# connectors.net
KiCad netlist of a schematic drawn in Altium Designer
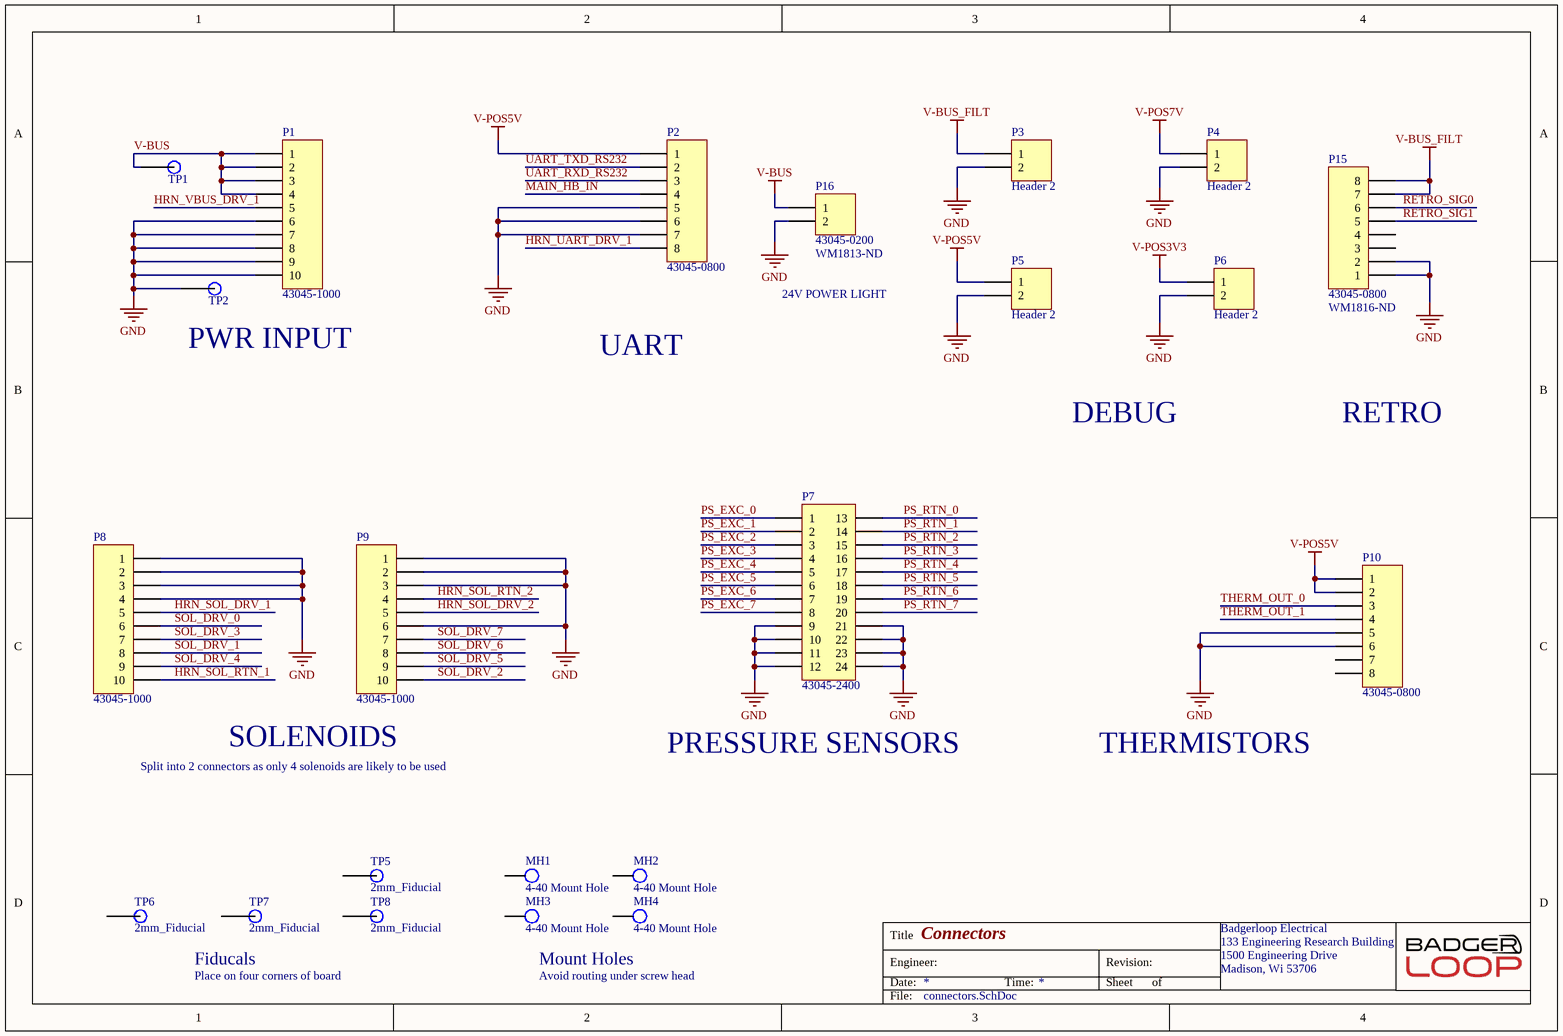
[diagram p0: connectors.SchDoc]

(export (version "E")
  (design (tool "Eeschema 10.0.6"))
  (components
    (comp (ref "MH1")
      (value "4-40 Mount Hole")
      (footprint "MH")
      (libsource (lib "misc") (part "4-40 Mount Hole"))
    )
    (comp (ref "MH2")
      (value "4-40 Mount Hole")
      (footprint "MH")
      (libsource (lib "misc") (part "4-40 Mount Hole"))
    )
    (comp (ref "MH3")
      (value "4-40 Mount Hole")
      (footprint "MH")
      (libsource (lib "misc") (part "4-40 Mount Hole"))
    )
    (comp (ref "MH4")
      (value "4-40 Mount Hole")
      (footprint "MH")
      (libsource (lib "misc") (part "4-40 Mount Hole"))
    )
    (comp (ref "P1")
      (value "43045-1000")
      (footprint "430451000")
      (description "GLOVE, POLYAMIDE, L/FREE, PU, SIZE 6 - More Details")
      (fields (field (name "MANUFACTURER") "Molex"))
      (libsource (lib "") (part "43045-1000_1"))
    )
    (comp (ref "P2")
      (value "43045-0800")
      (footprint "430450800")
      (description "CONN HEADER R/A 8POS 3MM")
      (fields (field (name "MANUFACTURER") "Molex"))
      (libsource (lib "connector") (part "43045-0800"))
    )
    (comp (ref "P3")
      (value "Header 2")
      (footprint "Pin Header 1x2 TH Pitch 2.54mm")
      (description "Header, 2-Pin")
      (fields (field (name "PUBLISHER") "Altium Limited"))
      (libsource (lib "connector") (part "Header 2"))
    )
    (comp (ref "P4")
      (value "Header 2")
      (footprint "Pin Header 1x2 TH Pitch 2.54mm")
      (description "Header, 2-Pin")
      (fields (field (name "PUBLISHER") "Altium Limited"))
      (libsource (lib "connector") (part "Header 2"))
    )
    (comp (ref "P5")
      (value "Header 2")
      (footprint "Pin Header 1x2 TH Pitch 2.54mm")
      (description "Header, 2-Pin")
      (fields (field (name "PUBLISHER") "Altium Limited"))
      (libsource (lib "connector") (part "Header 2"))
    )
    (comp (ref "P6")
      (value "Header 2")
      (footprint "Pin Header 1x2 TH Pitch 2.54mm")
      (description "Header, 2-Pin")
      (fields (field (name "PUBLISHER") "Altium Limited"))
      (libsource (lib "connector") (part "Header 2"))
    )
    (comp (ref "P7")
      (value "43045-2400")
      (footprint "430452400")
      (fields (field (name "MANUFACTURER") "Molex"))
      (libsource (lib "connector") (part "43045-2400"))
    )
    (comp (ref "P8")
      (value "43045-1000")
      (footprint "430451000")
      (description "GLOVE, POLYAMIDE, L/FREE, PU, SIZE 6 - More Details")
      (fields (field (name "MANUFACTURER") "Molex"))
      (libsource (lib "connector") (part "43045-1000"))
    )
    (comp (ref "P9")
      (value "43045-1000")
      (footprint "430451000")
      (description "GLOVE, POLYAMIDE, L/FREE, PU, SIZE 6 - More Details")
      (fields (field (name "MANUFACTURER") "Molex"))
      (libsource (lib "connector") (part "43045-1000"))
    )
    (comp (ref "P10")
      (value "43045-0800")
      (footprint "430450800")
      (description "CONN HEADER R/A 8POS 3MM")
      (fields (field (name "MANUFACTURER") "Molex"))
      (libsource (lib "connector") (part "43045-0800"))
    )
    (comp (ref "P15")
      (value "43045-0800")
      (footprint "430450800")
      (description "CONN HEADER R/A 8POS 3MM")
      (fields (field (name "MANUFACTURER") "Molex") (field (name "SUPPLIER PART NUMBER 1") "WM1816-ND"))
      (libsource (lib "") (part "43045-0800_1"))
    )
    (comp (ref "P16")
      (value "43045-0200")
      (footprint "430450200")
      (description "CONN HEADER R/A 2POS")
      (fields (field (name "MANUFACTURER") "Molex") (field (name "SUPPLIER PART NUMBER 1") "WM1813-ND"))
      (libsource (lib "connector") (part "43045-0200"))
    )
    (comp (ref "TP1")
      (value "TP")
      (footprint "Test Point")
      (description "SMD TEST POINT")
      (libsource (lib "misc") (part "TP"))
    )
    (comp (ref "TP2")
      (value "TP")
      (footprint "Test Point")
      (description "SMD TEST POINT")
      (libsource (lib "misc") (part "TP"))
    )
    (comp (ref "TP5")
      (value "2mm_Fiducial")
      (footprint "2mm_Fiducial")
      (libsource (lib "misc") (part "2mm_Fiducial"))
    )
    (comp (ref "TP6")
      (value "2mm_Fiducial")
      (footprint "2mm_Fiducial")
      (libsource (lib "misc") (part "2mm_Fiducial"))
    )
    (comp (ref "TP7")
      (value "2mm_Fiducial")
      (footprint "2mm_Fiducial")
      (libsource (lib "misc") (part "2mm_Fiducial"))
    )
    (comp (ref "TP8")
      (value "2mm_Fiducial")
      (footprint "2mm_Fiducial")
      (libsource (lib "misc") (part "2mm_Fiducial"))
    )
  )
  (nets
    (net (code "1") (name "/HRN_SOL_DRV_1") (class "Default")
      (node (ref "P8") (pin "5") (pinfunction "5_5") (pintype "passive"))
    )
    (net (code "2") (name "/HRN_SOL_DRV_2") (class "Default")
      (node (ref "P9") (pin "5") (pinfunction "5_5") (pintype "passive"))
    )
    (net (code "3") (name "/HRN_SOL_RTN_1") (class "Default")
      (node (ref "P8") (pin "10") (pinfunction "10_10") (pintype "passive"))
    )
    (net (code "4") (name "/HRN_SOL_RTN_2") (class "Default")
      (node (ref "P9") (pin "4") (pinfunction "4_4") (pintype "passive"))
    )
    (net (code "5") (name "/HRN_UART_DRV_1") (class "Default")
      (node (ref "P2") (pin "8") (pinfunction "8_8") (pintype "passive"))
    )
    (net (code "6") (name "/HRN_VBUS_DRV_1") (class "Default")
      (node (ref "P1") (pin "5") (pinfunction "5_5") (pintype "passive"))
    )
    (net (code "7") (name "/MAIN_HB_IN") (class "Default")
      (node (ref "P2") (pin "4") (pinfunction "4_4") (pintype "passive"))
    )
    (net (code "8") (name "/PS_EXC_0") (class "Default")
      (node (ref "P7") (pin "1") (pinfunction "1_1") (pintype "passive"))
    )
    (net (code "9") (name "/PS_EXC_1") (class "Default")
      (node (ref "P7") (pin "2") (pinfunction "2_2") (pintype "passive"))
    )
    (net (code "10") (name "/PS_EXC_2") (class "Default")
      (node (ref "P7") (pin "3") (pinfunction "3_3") (pintype "passive"))
    )
    (net (code "11") (name "/PS_EXC_3") (class "Default")
      (node (ref "P7") (pin "4") (pinfunction "4_4") (pintype "passive"))
    )
    (net (code "12") (name "/PS_EXC_4") (class "Default")
      (node (ref "P7") (pin "5") (pinfunction "5_5") (pintype "passive"))
    )
    (net (code "13") (name "/PS_EXC_5") (class "Default")
      (node (ref "P7") (pin "6") (pinfunction "6_6") (pintype "passive"))
    )
    (net (code "14") (name "/PS_EXC_6") (class "Default")
      (node (ref "P7") (pin "7") (pinfunction "7_7") (pintype "passive"))
    )
    (net (code "15") (name "/PS_EXC_7") (class "Default")
      (node (ref "P7") (pin "8") (pinfunction "8_8") (pintype "passive"))
    )
    (net (code "16") (name "/PS_RTN_0") (class "Default")
      (node (ref "P7") (pin "13") (pinfunction "13_13") (pintype "passive"))
    )
    (net (code "17") (name "/PS_RTN_1") (class "Default")
      (node (ref "P7") (pin "14") (pinfunction "14_14") (pintype "passive"))
    )
    (net (code "18") (name "/PS_RTN_2") (class "Default")
      (node (ref "P7") (pin "15") (pinfunction "15_15") (pintype "passive"))
    )
    (net (code "19") (name "/PS_RTN_3") (class "Default")
      (node (ref "P7") (pin "16") (pinfunction "16_16") (pintype "passive"))
    )
    (net (code "20") (name "/PS_RTN_4") (class "Default")
      (node (ref "P7") (pin "17") (pinfunction "17_17") (pintype "passive"))
    )
    (net (code "21") (name "/PS_RTN_5") (class "Default")
      (node (ref "P7") (pin "18") (pinfunction "18_18") (pintype "passive"))
    )
    (net (code "22") (name "/PS_RTN_6") (class "Default")
      (node (ref "P7") (pin "19") (pinfunction "19_19") (pintype "passive"))
    )
    (net (code "23") (name "/PS_RTN_7") (class "Default")
      (node (ref "P7") (pin "20") (pinfunction "20_20") (pintype "passive"))
    )
    (net (code "24") (name "/RETRO_SIG0") (class "Default")
      (node (ref "P15") (pin "6") (pinfunction "6_6") (pintype "passive"))
    )
    (net (code "25") (name "/RETRO_SIG1") (class "Default")
      (node (ref "P15") (pin "5") (pinfunction "5_5") (pintype "passive"))
    )
    (net (code "26") (name "/SOL_DRV_0") (class "Default")
      (node (ref "P8") (pin "6") (pinfunction "6_6") (pintype "passive"))
    )
    (net (code "27") (name "/SOL_DRV_1") (class "Default")
      (node (ref "P8") (pin "8") (pinfunction "8_8") (pintype "passive"))
    )
    (net (code "28") (name "/SOL_DRV_2") (class "Default")
      (node (ref "P9") (pin "10") (pinfunction "10_10") (pintype "passive"))
    )
    (net (code "29") (name "/SOL_DRV_3") (class "Default")
      (node (ref "P8") (pin "7") (pinfunction "7_7") (pintype "passive"))
    )
    (net (code "30") (name "/SOL_DRV_4") (class "Default")
      (node (ref "P8") (pin "9") (pinfunction "9_9") (pintype "passive"))
    )
    (net (code "31") (name "/SOL_DRV_5") (class "Default")
      (node (ref "P9") (pin "9") (pinfunction "9_9") (pintype "passive"))
    )
    (net (code "32") (name "/SOL_DRV_6") (class "Default")
      (node (ref "P9") (pin "8") (pinfunction "8_8") (pintype "passive"))
    )
    (net (code "33") (name "/SOL_DRV_7") (class "Default")
      (node (ref "P9") (pin "7") (pinfunction "7_7") (pintype "passive"))
    )
    (net (code "34") (name "/THERM_OUT_0") (class "Default")
      (node (ref "P10") (pin "3") (pinfunction "3_3") (pintype "passive"))
    )
    (net (code "35") (name "/THERM_OUT_1") (class "Default")
      (node (ref "P10") (pin "4") (pinfunction "4_4") (pintype "passive"))
    )
    (net (code "36") (name "/UART_RXD_RS232") (class "Default")
      (node (ref "P2") (pin "3") (pinfunction "3_3") (pintype "passive"))
    )
    (net (code "37") (name "/UART_TXD_RS232") (class "Default")
      (node (ref "P2") (pin "2") (pinfunction "2_2") (pintype "passive"))
    )
    (net (code "38") (name "GND") (class "Default")
      (node (ref "P1") (pin "10") (pinfunction "10_10") (pintype "passive"))
      (node (ref "P1") (pin "6") (pinfunction "6_6") (pintype "passive"))
      (node (ref "P1") (pin "7") (pinfunction "7_7") (pintype "passive"))
      (node (ref "P1") (pin "8") (pinfunction "8_8") (pintype "passive"))
      (node (ref "P1") (pin "9") (pinfunction "9_9") (pintype "passive"))
      (node (ref "P10") (pin "5") (pinfunction "5_5") (pintype "passive"))
      (node (ref "P10") (pin "6") (pinfunction "6_6") (pintype "passive"))
      (node (ref "P15") (pin "1") (pinfunction "1_1") (pintype "passive"))
      (node (ref "P15") (pin "2") (pinfunction "2_2") (pintype "passive"))
      (node (ref "P16") (pin "2") (pinfunction "2_2") (pintype "passive"))
      (node (ref "P2") (pin "5") (pinfunction "5_5") (pintype "passive"))
      (node (ref "P2") (pin "6") (pinfunction "6_6") (pintype "passive"))
      (node (ref "P2") (pin "7") (pinfunction "7_7") (pintype "passive"))
      (node (ref "P3") (pin "2") (pinfunction "2_2") (pintype "passive"))
      (node (ref "P4") (pin "2") (pinfunction "2_2") (pintype "passive"))
      (node (ref "P5") (pin "2") (pinfunction "2_2") (pintype "passive"))
      (node (ref "P6") (pin "2") (pinfunction "2_2") (pintype "passive"))
      (node (ref "P7") (pin "10") (pinfunction "10_10") (pintype "passive"))
      (node (ref "P7") (pin "11") (pinfunction "11_11") (pintype "passive"))
      (node (ref "P7") (pin "12") (pinfunction "12_12") (pintype "passive"))
      (node (ref "P7") (pin "21") (pinfunction "21_21") (pintype "passive"))
      (node (ref "P7") (pin "22") (pinfunction "22_22") (pintype "passive"))
      (node (ref "P7") (pin "23") (pinfunction "23_23") (pintype "passive"))
      (node (ref "P7") (pin "24") (pinfunction "24_24") (pintype "passive"))
      (node (ref "P7") (pin "9") (pinfunction "9_9") (pintype "passive"))
      (node (ref "P8") (pin "1") (pinfunction "1_1") (pintype "passive"))
      (node (ref "P8") (pin "2") (pinfunction "2_2") (pintype "passive"))
      (node (ref "P8") (pin "3") (pinfunction "3_3") (pintype "passive"))
      (node (ref "P8") (pin "4") (pinfunction "4_4") (pintype "passive"))
      (node (ref "P9") (pin "1") (pinfunction "1_1") (pintype "passive"))
      (node (ref "P9") (pin "2") (pinfunction "2_2") (pintype "passive"))
      (node (ref "P9") (pin "3") (pinfunction "3_3") (pintype "passive"))
      (node (ref "P9") (pin "6") (pinfunction "6_6") (pintype "passive"))
      (node (ref "TP2") (pin "1") (pinfunction "1_1") (pintype "passive"))
    )
    (net (code "39") (name "V-BUS") (class "Default")
      (node (ref "P1") (pin "1") (pinfunction "1_1") (pintype "passive"))
      (node (ref "P1") (pin "2") (pinfunction "2_2") (pintype "passive"))
      (node (ref "P1") (pin "3") (pinfunction "3_3") (pintype "passive"))
      (node (ref "P1") (pin "4") (pinfunction "4_4") (pintype "passive"))
      (node (ref "P16") (pin "1") (pinfunction "1_1") (pintype "passive"))
      (node (ref "TP1") (pin "1") (pinfunction "1_1") (pintype "passive"))
    )
    (net (code "40") (name "V-BUS_FILT") (class "Default")
      (node (ref "P15") (pin "7") (pinfunction "7_7") (pintype "passive"))
      (node (ref "P15") (pin "8") (pinfunction "8_8") (pintype "passive"))
      (node (ref "P3") (pin "1") (pinfunction "1_1") (pintype "passive"))
    )
    (net (code "41") (name "V-POS3V3") (class "Default")
      (node (ref "P6") (pin "1") (pinfunction "1_1") (pintype "passive"))
    )
    (net (code "42") (name "V-POS5V") (class "Default")
      (node (ref "P10") (pin "1") (pinfunction "1_1") (pintype "passive"))
      (node (ref "P10") (pin "2") (pinfunction "2_2") (pintype "passive"))
      (node (ref "P2") (pin "1") (pinfunction "1_1") (pintype "passive"))
      (node (ref "P5") (pin "1") (pinfunction "1_1") (pintype "passive"))
    )
    (net (code "43") (name "V-POS7V") (class "Default")
      (node (ref "P4") (pin "1") (pinfunction "1_1") (pintype "passive"))
    )
    (net (code "44") (name "unconnected-(MH1-Pad46)") (class "Default")
      (node (ref "MH1") (pin "46") (pinfunction "46_46") (pintype "passive"))
    )
    (net (code "45") (name "unconnected-(MH2-Pad46)") (class "Default")
      (node (ref "MH2") (pin "46") (pinfunction "46_46") (pintype "passive"))
    )
    (net (code "46") (name "unconnected-(MH3-Pad46)") (class "Default")
      (node (ref "MH3") (pin "46") (pinfunction "46_46") (pintype "passive"))
    )
    (net (code "47") (name "unconnected-(MH4-Pad46)") (class "Default")
      (node (ref "MH4") (pin "46") (pinfunction "46_46") (pintype "passive"))
    )
    (net (code "48") (name "unconnected-(P10-Pad7)") (class "Default")
      (node (ref "P10") (pin "7") (pinfunction "7_7") (pintype "passive"))
    )
    (net (code "49") (name "unconnected-(P10-Pad8)") (class "Default")
      (node (ref "P10") (pin "8") (pinfunction "8_8") (pintype "passive"))
    )
    (net (code "50") (name "unconnected-(P15-Pad3)") (class "Default")
      (node (ref "P15") (pin "3") (pinfunction "3_3") (pintype "passive"))
    )
    (net (code "51") (name "unconnected-(P15-Pad4)") (class "Default")
      (node (ref "P15") (pin "4") (pinfunction "4_4") (pintype "passive"))
    )
    (net (code "52") (name "unconnected-(TP5-Pad1)") (class "Default")
      (node (ref "TP5") (pin "1") (pinfunction "1_1") (pintype "passive"))
    )
    (net (code "53") (name "unconnected-(TP6-Pad1)") (class "Default")
      (node (ref "TP6") (pin "1") (pinfunction "1_1") (pintype "passive"))
    )
    (net (code "54") (name "unconnected-(TP7-Pad1)") (class "Default")
      (node (ref "TP7") (pin "1") (pinfunction "1_1") (pintype "passive"))
    )
    (net (code "55") (name "unconnected-(TP8-Pad1)") (class "Default")
      (node (ref "TP8") (pin "1") (pinfunction "1_1") (pintype "passive"))
    )
  )
)
